# Ethernet.net
KiCad netlist of a schematic drawn in Altium Designer
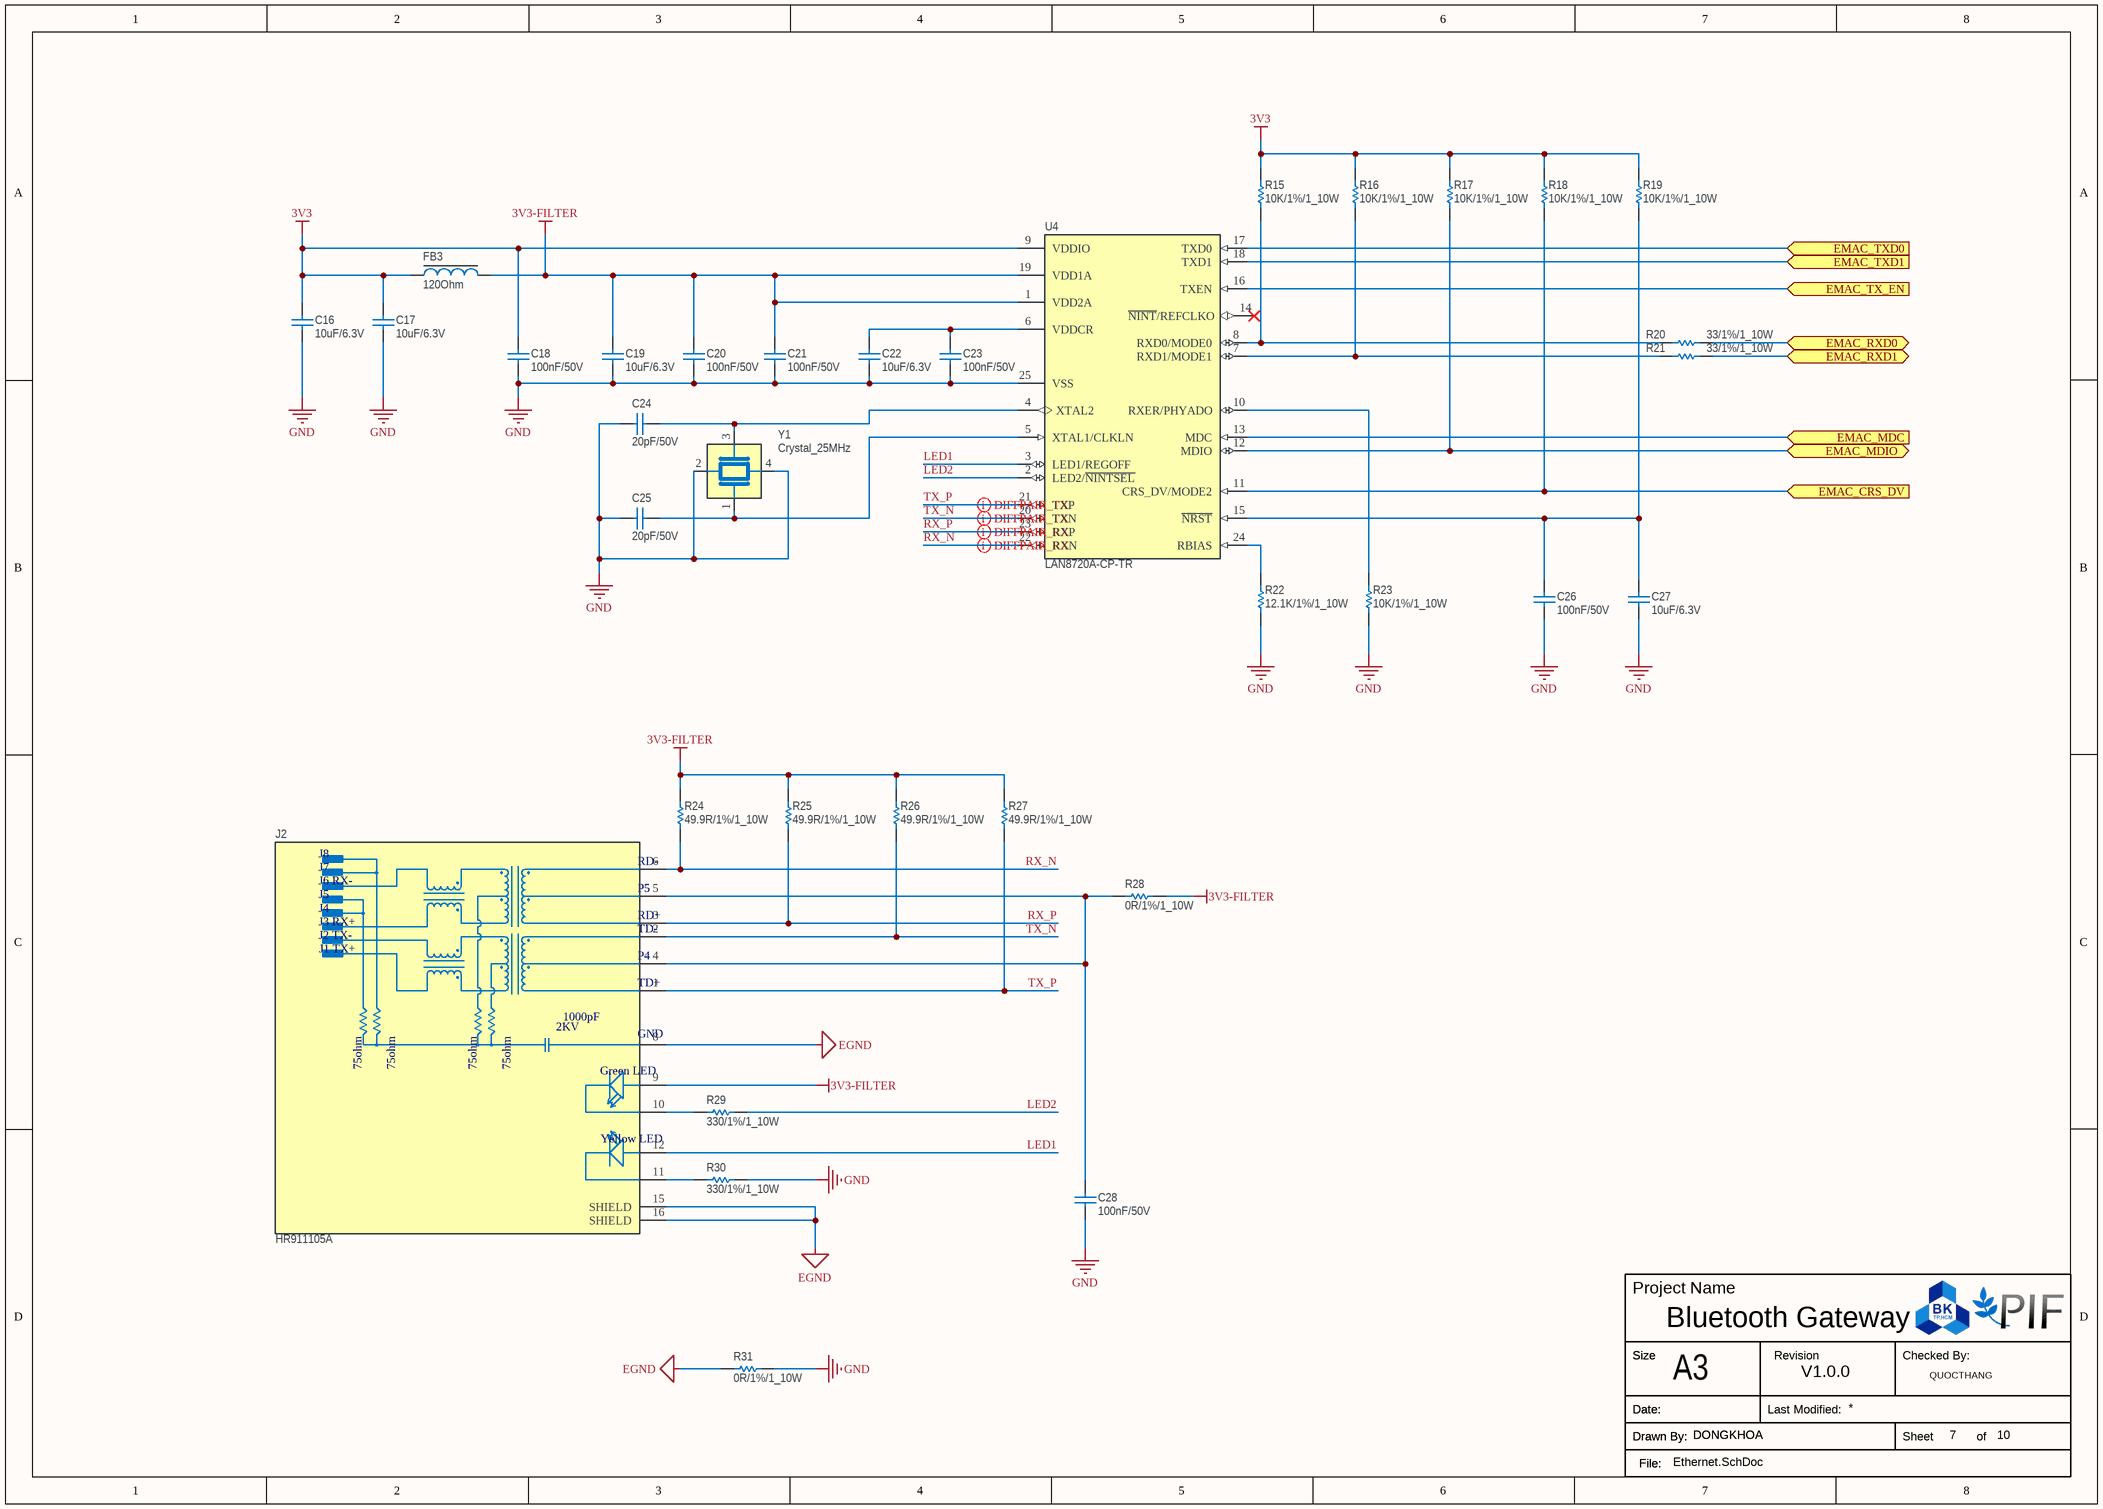
[diagram p0: Ethernet.SchDoc]

(export (version "E")
  (design (tool "Eeschema 10.0.6"))
  (components
    (comp (ref "C16")
      (value "10uF/6.3V")
      (footprint "CAP_0603")
      (description "CAP, size 0603, 10uF, 6.3V")
      (fields (field (name "SUPPLY PART NUMBER") "CC0603KRX5R5BB106"))
      (libsource (lib "BluetoothTracking") (part "Ceramic_Cap_10uF_6.3V_0603"))
    )
    (comp (ref "C17")
      (value "10uF/6.3V")
      (footprint "CAP_0603")
      (description "CAP, size 0603, 10uF, 6.3V")
      (fields (field (name "SUPPLY PART NUMBER") "CC0603KRX5R5BB106"))
      (libsource (lib "BluetoothTracking") (part "Ceramic_Cap_10uF_6.3V_0603"))
    )
    (comp (ref "C18")
      (value "100nF/50V")
      (footprint "CAP_0603")
      (description "CAP, size 0603, 100nF, 50V")
      (fields (field (name "SUPPLY PART NUMBER") "Tụ Gốm 0603 100nF (0.1uF) 50V"))
      (libsource (lib "BluetoothTracking") (part "Ceramic_Cap_100nF_50V_0603"))
    )
    (comp (ref "C19")
      (value "10uF/6.3V")
      (footprint "CAP_0603")
      (description "CAP, size 0603, 10uF, 6.3V")
      (fields (field (name "SUPPLY PART NUMBER") "CC0603KRX5R5BB106"))
      (libsource (lib "BluetoothTracking") (part "Ceramic_Cap_10uF_6.3V_0603"))
    )
    (comp (ref "C20")
      (value "100nF/50V")
      (footprint "CAP_0603")
      (description "CAP, size 0603, 100nF, 50V")
      (fields (field (name "SUPPLY PART NUMBER") "Tụ Gốm 0603 100nF (0.1uF) 50V"))
      (libsource (lib "BluetoothTracking") (part "Ceramic_Cap_100nF_50V_0603"))
    )
    (comp (ref "C21")
      (value "100nF/50V")
      (footprint "CAP_0603")
      (description "CAP, size 0603, 100nF, 50V")
      (fields (field (name "SUPPLY PART NUMBER") "Tụ Gốm 0603 100nF (0.1uF) 50V"))
      (libsource (lib "BluetoothTracking") (part "Ceramic_Cap_100nF_50V_0603"))
    )
    (comp (ref "C22")
      (value "10uF/6.3V")
      (footprint "CAP_0603")
      (description "CAP, size 0603, 10uF, 6.3V")
      (fields (field (name "SUPPLY PART NUMBER") "CC0603KRX5R5BB106"))
      (libsource (lib "BluetoothTracking") (part "Ceramic_Cap_10uF_6.3V_0603"))
    )
    (comp (ref "C23")
      (value "100nF/50V")
      (footprint "CAP_0603")
      (description "CAP, size 0603, 100nF, 50V")
      (fields (field (name "SUPPLY PART NUMBER") "Tụ Gốm 0603 100nF (0.1uF) 50V"))
      (libsource (lib "BluetoothTracking") (part "Ceramic_Cap_100nF_50V_0603"))
    )
    (comp (ref "C24")
      (value "20pF/50V")
      (footprint "CAP_0603")
      (description "CAP, size 0603, 20pF, 50V")
      (fields (field (name "SUPPLY PART NUMBER") "CC0603JRNPO9BN200"))
      (libsource (lib "BluetoothTracking") (part "Ceramic_Cap_20pF_50V_0603"))
    )
    (comp (ref "C25")
      (value "20pF/50V")
      (footprint "CAP_0603")
      (description "CAP, size 0603, 20pF, 50V")
      (fields (field (name "SUPPLY PART NUMBER") "CC0603JRNPO9BN200"))
      (libsource (lib "BluetoothTracking") (part "Ceramic_Cap_20pF_50V_0603"))
    )
    (comp (ref "C26")
      (value "100nF/50V")
      (footprint "CAP_0603")
      (description "CAP, size 0603, 100nF, 50V")
      (fields (field (name "SUPPLY PART NUMBER") "Tụ Gốm 0603 100nF (0.1uF) 50V"))
      (libsource (lib "BluetoothTracking") (part "Ceramic_Cap_100nF_50V_0603"))
    )
    (comp (ref "C27")
      (value "10uF/6.3V")
      (footprint "CAP_0603")
      (description "CAP, size 0603, 10uF, 6.3V")
      (fields (field (name "SUPPLY PART NUMBER") "CC0603KRX5R5BB106"))
      (libsource (lib "BluetoothTracking") (part "Ceramic_Cap_10uF_6.3V_0603"))
    )
    (comp (ref "C28")
      (value "100nF/50V")
      (footprint "CAP_0603")
      (description "CAP, size 0603, 100nF, 50V")
      (fields (field (name "SUPPLY PART NUMBER") "Tụ Gốm 0603 100nF (0.1uF) 50V"))
      (libsource (lib "BluetoothTracking") (part "Ceramic_Cap_100nF_50V_0603"))
    )
    (comp (ref "FB3")
      (value "120Ohm")
      (footprint "Ferrite_Bead_0805")
      (description "Ferrite Bead, size 0805, 120Ohm, 2A")
      (fields (field (name "SUPPLY PART NUMBER") "CBW201209U121T Ferrite Beads 2A 120 Ohm 0805"))
      (libsource (lib "BluetoothTracking") (part "Ferrite_Bead_120Ohm_2A_0805"))
    )
    (comp (ref "J2")
      (value "HR911105A")
      (footprint "HANRUN_HR911105A")
      (description "DIP RJ45 Connector;")
      (fields (field (name "SUPPLY PART NUMBER") "HR911105A Cổng RJ45 Cái Có LED Hanrun"))
      (libsource (lib "BluetoothTracking") (part "HR911105A"))
    )
    (comp (ref "R15")
      (value "10K/1%/1_10W")
      (footprint "Resistor_0603")
      (description "Resistor 0603 10KOhm 1% 1_10W")
      (fields (field (name "SUPPLY PART NUMBER") "Điện Trở 10 KOhm 0603 1%"))
      (libsource (lib "BluetoothTracking") (part "Res_10K_0603_1%"))
    )
    (comp (ref "R16")
      (value "10K/1%/1_10W")
      (footprint "Resistor_0603")
      (description "Resistor 0603 10KOhm 1% 1_10W")
      (fields (field (name "SUPPLY PART NUMBER") "Điện Trở 10 KOhm 0603 1%"))
      (libsource (lib "BluetoothTracking") (part "Res_10K_0603_1%"))
    )
    (comp (ref "R17")
      (value "10K/1%/1_10W")
      (footprint "Resistor_0603")
      (description "Resistor 0603 10KOhm 1% 1_10W")
      (fields (field (name "SUPPLY PART NUMBER") "Điện Trở 10 KOhm 0603 1%"))
      (libsource (lib "BluetoothTracking") (part "Res_10K_0603_1%"))
    )
    (comp (ref "R18")
      (value "10K/1%/1_10W")
      (footprint "Resistor_0603")
      (description "Resistor 0603 10KOhm 1% 1_10W")
      (fields (field (name "SUPPLY PART NUMBER") "Điện Trở 10 KOhm 0603 1%"))
      (libsource (lib "BluetoothTracking") (part "Res_10K_0603_1%"))
    )
    (comp (ref "R19")
      (value "10K/1%/1_10W")
      (footprint "Resistor_0603")
      (description "Resistor 0603 10KOhm 1% 1_10W")
      (fields (field (name "SUPPLY PART NUMBER") "Điện Trở 10 KOhm 0603 1%"))
      (libsource (lib "BluetoothTracking") (part "Res_10K_0603_1%"))
    )
    (comp (ref "R20")
      (value "33/1%/1_10W")
      (footprint "Resistor_0603")
      (description "Resistor 0603 33Ohm 1% 1_10W")
      (fields (field (name "SUPPLY PART NUMBER") "Điện Trở 33 Ohm 0603 1%"))
      (libsource (lib "BluetoothTracking") (part "Res_33R_0603_1%"))
    )
    (comp (ref "R21")
      (value "33/1%/1_10W")
      (footprint "Resistor_0603")
      (description "Resistor 0603 33Ohm 1% 1_10W")
      (fields (field (name "SUPPLY PART NUMBER") "Điện Trở 33 Ohm 0603 1%"))
      (libsource (lib "BluetoothTracking") (part "Res_33R_0603_1%"))
    )
    (comp (ref "R22")
      (value "12.1K/1%/1_10W")
      (footprint "Resistor_0603")
      (description "Resistor 0603 12.1KOhm 1% 1_10W")
      (fields (field (name "SUPPLY PART NUMBER") "Điện Trở 12.1 KOhm 0603 1%"))
      (libsource (lib "BluetoothTracking") (part "Res_12.1K_0603_1%"))
    )
    (comp (ref "R23")
      (value "10K/1%/1_10W")
      (footprint "Resistor_0603")
      (description "Resistor 0603 10KOhm 1% 1_10W")
      (fields (field (name "SUPPLY PART NUMBER") "Điện Trở 10 KOhm 0603 1%"))
      (libsource (lib "BluetoothTracking") (part "Res_10K_0603_1%"))
    )
    (comp (ref "R24")
      (value "49.9R/1%/1_10W")
      (footprint "Resistor_0603")
      (description "Resistor 0603 49.9 Ohm 1% 1_10W")
      (fields (field (name "SUPPLY PART NUMBER") "Điện Trở 49.9 Ohm 0603 1%"))
      (libsource (lib "BluetoothTracking") (part "Res_49.9R_0603_1%"))
    )
    (comp (ref "R25")
      (value "49.9R/1%/1_10W")
      (footprint "Resistor_0603")
      (description "Resistor 0603 49.9 Ohm 1% 1_10W")
      (fields (field (name "SUPPLY PART NUMBER") "Điện Trở 49.9 Ohm 0603 1%"))
      (libsource (lib "BluetoothTracking") (part "Res_49.9R_0603_1%"))
    )
    (comp (ref "R26")
      (value "49.9R/1%/1_10W")
      (footprint "Resistor_0603")
      (description "Resistor 0603 49.9 Ohm 1% 1_10W")
      (fields (field (name "SUPPLY PART NUMBER") "Điện Trở 49.9 Ohm 0603 1%"))
      (libsource (lib "BluetoothTracking") (part "Res_49.9R_0603_1%"))
    )
    (comp (ref "R27")
      (value "49.9R/1%/1_10W")
      (footprint "Resistor_0603")
      (description "Resistor 0603 49.9 Ohm 1% 1_10W")
      (fields (field (name "SUPPLY PART NUMBER") "Điện Trở 49.9 Ohm 0603 1%"))
      (libsource (lib "BluetoothTracking") (part "Res_49.9R_0603_1%"))
    )
    (comp (ref "R28")
      (value "0R/1%/1_10W")
      (footprint "Resistor_0603")
      (description "Resistor 0603 0 Ohm 1% 1_10W")
      (fields (field (name "SUPPLY PART NUMBER") "Điện Trở 0 Ohm 0603 1%"))
      (libsource (lib "BluetoothTracking") (part "Res_0R_0603_1%"))
    )
    (comp (ref "R29")
      (value "330/1%/1_10W")
      (footprint "Resistor_0603")
      (description "Resistor 0603 330KOhm 1% 1_10W")
      (fields (field (name "SUPPLY PART NUMBER") "Điện Trở 330 Ohm 0603 1%"))
      (libsource (lib "BluetoothTracking") (part "Res_330_0603_1%"))
    )
    (comp (ref "R30")
      (value "330/1%/1_10W")
      (footprint "Resistor_0603")
      (description "Resistor 0603 330KOhm 1% 1_10W")
      (fields (field (name "SUPPLY PART NUMBER") "Điện Trở 330 Ohm 0603 1%"))
      (libsource (lib "BluetoothTracking") (part "Res_330_0603_1%"))
    )
    (comp (ref "R31")
      (value "0R/1%/1_10W")
      (footprint "Resistor_0603")
      (description "Resistor 0603 0 Ohm 1% 1_10W")
      (fields (field (name "SUPPLY PART NUMBER") "Điện Trở 0 Ohm 0603 1%"))
      (libsource (lib "BluetoothTracking") (part "Res_0R_0603_1%"))
    )
    (comp (ref "U4")
      (value "LAN8720A-CP-TR")
      (footprint "QFN-EP-24")
      (description "PHY 1-CH 10Mbps/100Mbps 2.5V/3.3V 24-PinQFN EP Tray")
      (fields (field (name "SUPPLY PART NUMBER") "LAN8720A IC Truyền Nhận Ethernet 24-QFN"))
      (libsource (lib "BluetoothTracking") (part "LAN8720A-CP-TR"))
    )
    (comp (ref "Y1")
      (value "Crystal_25MHz")
      (footprint "Crystal_SMD_3225_4P")
      (description "25 MHz Crystal 4-SMD")
      (fields (field (name "SUPPLY PART NUMBER") "Thạch Anh 25MHz 3225 4 Chân SMD"))
      (libsource (lib "BluetoothTracking") (part "Crystal_25MHz"))
    )
  )
  (nets
    (net (code "1") (name "/EMAC_CRS_DV") (class "Default")
      (node (ref "R18") (pin "1") (pinfunction "1_1") (pintype "passive"))
      (node (ref "U4") (pin "11") (pinfunction "CRS_DV/MODE2_11") (pintype "input"))
    )
    (net (code "2") (name "/EMAC_MDC") (class "Default")
      (node (ref "U4") (pin "13") (pinfunction "MDC_13") (pintype "input"))
    )
    (net (code "3") (name "/EMAC_MDIO") (class "Default")
      (node (ref "R17") (pin "1") (pinfunction "1_1") (pintype "passive"))
      (node (ref "U4") (pin "12") (pinfunction "MDIO_12") (pintype "bidirectional"))
    )
    (net (code "4") (name "/EMAC_RXD0") (class "Default")
      (node (ref "R20") (pin "2") (pinfunction "2_2") (pintype "passive"))
    )
    (net (code "5") (name "/EMAC_RXD1") (class "Default")
      (node (ref "R21") (pin "2") (pinfunction "2_2") (pintype "passive"))
    )
    (net (code "6") (name "/EMAC_TXD0") (class "Default")
      (node (ref "U4") (pin "17") (pinfunction "TXD0_17") (pintype "input"))
    )
    (net (code "7") (name "/EMAC_TXD1") (class "Default")
      (node (ref "U4") (pin "18") (pinfunction "TXD1_18") (pintype "input"))
    )
    (net (code "8") (name "/EMAC_TX_EN") (class "Default")
      (node (ref "U4") (pin "16") (pinfunction "TXEN_16") (pintype "input"))
    )
    (net (code "9") (name "/LED1") (class "Default")
      (node (ref "J2") (pin "12") (pinfunction "YA_12") (pintype "passive"))
      (node (ref "U4") (pin "3") (pinfunction "LED1/REGOFF_3") (pintype "bidirectional"))
    )
    (net (code "10") (name "/LED2") (class "Default")
      (node (ref "R29") (pin "2") (pinfunction "2_2") (pintype "passive"))
      (node (ref "U4") (pin "2") (pinfunction "LED2/~{NINTSEL}_2") (pintype "bidirectional"))
    )
    (net (code "11") (name "/RX_N") (class "Default")
      (node (ref "J2") (pin "6") (pinfunction "RD-_6") (pintype "passive"))
      (node (ref "R24") (pin "1") (pinfunction "1_1") (pintype "passive"))
      (node (ref "U4") (pin "22") (pinfunction "RXN_22") (pintype "bidirectional"))
    )
    (net (code "12") (name "/RX_P") (class "Default")
      (node (ref "J2") (pin "3") (pinfunction "RD+_3") (pintype "passive"))
      (node (ref "R25") (pin "1") (pinfunction "1_1") (pintype "passive"))
      (node (ref "U4") (pin "23") (pinfunction "RXP_23") (pintype "bidirectional"))
    )
    (net (code "13") (name "/TX_N") (class "Default")
      (node (ref "J2") (pin "2") (pinfunction "TD-_2") (pintype "passive"))
      (node (ref "R26") (pin "1") (pinfunction "1_1") (pintype "passive"))
      (node (ref "U4") (pin "20") (pinfunction "TXN_20") (pintype "bidirectional"))
    )
    (net (code "14") (name "/TX_P") (class "Default")
      (node (ref "J2") (pin "1") (pinfunction "TD+_1") (pintype "passive"))
      (node (ref "R27") (pin "1") (pinfunction "1_1") (pintype "passive"))
      (node (ref "U4") (pin "21") (pinfunction "TXP_21") (pintype "bidirectional"))
    )
    (net (code "15") (name "3V3") (class "Default")
      (node (ref "C16") (pin "2") (pinfunction "2_2") (pintype "passive"))
      (node (ref "C17") (pin "2") (pinfunction "2_2") (pintype "passive"))
      (node (ref "C18") (pin "2") (pinfunction "2_2") (pintype "passive"))
      (node (ref "FB3") (pin "1") (pinfunction "1_1") (pintype "passive"))
      (node (ref "R15") (pin "2") (pinfunction "2_2") (pintype "passive"))
      (node (ref "R16") (pin "2") (pinfunction "2_2") (pintype "passive"))
      (node (ref "R17") (pin "2") (pinfunction "2_2") (pintype "passive"))
      (node (ref "R18") (pin "2") (pinfunction "2_2") (pintype "passive"))
      (node (ref "R19") (pin "2") (pinfunction "2_2") (pintype "passive"))
      (node (ref "U4") (pin "9") (pinfunction "VDDIO_9") (pintype "power_in"))
    )
    (net (code "16") (name "3V3-FILTER") (class "Default")
      (node (ref "C19") (pin "2") (pinfunction "2_2") (pintype "passive"))
      (node (ref "C20") (pin "2") (pinfunction "2_2") (pintype "passive"))
      (node (ref "C21") (pin "2") (pinfunction "2_2") (pintype "passive"))
      (node (ref "FB3") (pin "2") (pinfunction "2_2") (pintype "passive"))
      (node (ref "J2") (pin "9") (pinfunction "GA_9") (pintype "passive"))
      (node (ref "R24") (pin "2") (pinfunction "2_2") (pintype "passive"))
      (node (ref "R25") (pin "2") (pinfunction "2_2") (pintype "passive"))
      (node (ref "R26") (pin "2") (pinfunction "2_2") (pintype "passive"))
      (node (ref "R27") (pin "2") (pinfunction "2_2") (pintype "passive"))
      (node (ref "R28") (pin "2") (pinfunction "2_2") (pintype "passive"))
      (node (ref "U4") (pin "1") (pinfunction "VDD2A_1") (pintype "power_in"))
      (node (ref "U4") (pin "19") (pinfunction "VDD1A_19") (pintype "power_in"))
    )
    (net (code "17") (name "EGND") (class "Default")
      (node (ref "J2") (pin "15") (pinfunction "SHIELD_15") (pintype "passive"))
      (node (ref "J2") (pin "16") (pinfunction "SHIELD_16") (pintype "passive"))
      (node (ref "J2") (pin "8") (pinfunction "GND_8") (pintype "power_in"))
      (node (ref "R31") (pin "1") (pinfunction "1_1") (pintype "passive"))
    )
    (net (code "18") (name "GND") (class "Default")
      (node (ref "C16") (pin "1") (pinfunction "1_1") (pintype "passive"))
      (node (ref "C17") (pin "1") (pinfunction "1_1") (pintype "passive"))
      (node (ref "C18") (pin "1") (pinfunction "1_1") (pintype "passive"))
      (node (ref "C19") (pin "1") (pinfunction "1_1") (pintype "passive"))
      (node (ref "C20") (pin "1") (pinfunction "1_1") (pintype "passive"))
      (node (ref "C21") (pin "1") (pinfunction "1_1") (pintype "passive"))
      (node (ref "C22") (pin "1") (pinfunction "1_1") (pintype "passive"))
      (node (ref "C23") (pin "1") (pinfunction "1_1") (pintype "passive"))
      (node (ref "C24") (pin "2") (pinfunction "2_2") (pintype "passive"))
      (node (ref "C25") (pin "1") (pinfunction "1_1") (pintype "passive"))
      (node (ref "C26") (pin "1") (pinfunction "1_1") (pintype "passive"))
      (node (ref "C27") (pin "1") (pinfunction "1_1") (pintype "passive"))
      (node (ref "C28") (pin "1") (pinfunction "1_1") (pintype "passive"))
      (node (ref "R22") (pin "1") (pinfunction "1_1") (pintype "passive"))
      (node (ref "R23") (pin "1") (pinfunction "1_1") (pintype "passive"))
      (node (ref "R30") (pin "2") (pinfunction "2_2") (pintype "passive"))
      (node (ref "R31") (pin "2") (pinfunction "2_2") (pintype "passive"))
      (node (ref "U4") (pin "25") (pinfunction "VSS_25") (pintype "power_in"))
      (node (ref "Y1") (pin "2") (pinfunction "GND_2") (pintype "power_in"))
      (node (ref "Y1") (pin "4") (pinfunction "GND_4") (pintype "power_in"))
    )
    (net (code "19") (name "Net-(J2-GC)") (class "Default")
      (node (ref "J2") (pin "10") (pinfunction "GC_10") (pintype "passive"))
      (node (ref "R29") (pin "1") (pinfunction "1_1") (pintype "passive"))
    )
    (net (code "20") (name "Net-(J2-P4)") (class "Default")
      (node (ref "C28") (pin "2") (pinfunction "2_2") (pintype "passive"))
      (node (ref "J2") (pin "4") (pinfunction "P4_4") (pintype "passive"))
      (node (ref "J2") (pin "5") (pinfunction "P5_5") (pintype "passive"))
      (node (ref "R28") (pin "1") (pinfunction "1_1") (pintype "passive"))
    )
    (net (code "21") (name "Net-(J2-YC)") (class "Default")
      (node (ref "J2") (pin "11") (pinfunction "YC_11") (pintype "passive"))
      (node (ref "R30") (pin "1") (pinfunction "1_1") (pintype "passive"))
    )
    (net (code "22") (name "Net-(U4-RBIAS)") (class "Default")
      (node (ref "R22") (pin "2") (pinfunction "2_2") (pintype "passive"))
      (node (ref "U4") (pin "24") (pinfunction "RBIAS_24") (pintype "input"))
    )
    (net (code "23") (name "Net-(U4-RXD0{slash}MODE0)") (class "Default")
      (node (ref "R15") (pin "1") (pinfunction "1_1") (pintype "passive"))
      (node (ref "R20") (pin "1") (pinfunction "1_1") (pintype "passive"))
      (node (ref "U4") (pin "8") (pinfunction "RXD0/MODE0_8") (pintype "bidirectional"))
    )
    (net (code "24") (name "Net-(U4-RXD1{slash}MODE1)") (class "Default")
      (node (ref "R16") (pin "1") (pinfunction "1_1") (pintype "passive"))
      (node (ref "R21") (pin "1") (pinfunction "1_1") (pintype "passive"))
      (node (ref "U4") (pin "7") (pinfunction "RXD1/MODE1_7") (pintype "bidirectional"))
    )
    (net (code "25") (name "Net-(U4-RXER{slash}PHYADO)") (class "Default")
      (node (ref "R23") (pin "2") (pinfunction "2_2") (pintype "passive"))
      (node (ref "U4") (pin "10") (pinfunction "RXER/PHYADO_10") (pintype "bidirectional"))
    )
    (net (code "26") (name "Net-(U4-VDDCR)") (class "Default")
      (node (ref "C22") (pin "2") (pinfunction "2_2") (pintype "passive"))
      (node (ref "C23") (pin "2") (pinfunction "2_2") (pintype "passive"))
      (node (ref "U4") (pin "6") (pinfunction "VDDCR_6") (pintype "power_in"))
    )
    (net (code "27") (name "Net-(U4-XTAL1{slash}CLKLN)") (class "Default")
      (node (ref "C25") (pin "2") (pinfunction "2_2") (pintype "passive"))
      (node (ref "U4") (pin "5") (pinfunction "XTAL1/CLKLN_5") (pintype "input"))
      (node (ref "Y1") (pin "1") (pinfunction "1_1") (pintype "passive"))
    )
    (net (code "28") (name "Net-(U4-XTAL2)") (class "Default")
      (node (ref "C24") (pin "1") (pinfunction "1_1") (pintype "passive"))
      (node (ref "U4") (pin "4") (pinfunction "XTAL2_4") (pintype "output"))
      (node (ref "Y1") (pin "3") (pinfunction "2_3") (pintype "passive"))
    )
    (net (code "29") (name "Net-(U4-~{NRST})") (class "Default")
      (node (ref "C26") (pin "2") (pinfunction "2_2") (pintype "passive"))
      (node (ref "C27") (pin "2") (pinfunction "2_2") (pintype "passive"))
      (node (ref "R19") (pin "1") (pinfunction "1_1") (pintype "passive"))
      (node (ref "U4") (pin "15") (pinfunction "~{NRST}_15") (pintype "input"))
    )
    (net (code "30") (name "unconnected-(U4-~{NINT}{slash}REFCLKO-Pad14)") (class "Default")
      (node (ref "U4") (pin "14") (pinfunction "~{NINT}/REFCLKO_14") (pintype "output+no_connect"))
    )
  )
)
